# Optotransistor.net
KiCad netlist of a schematic drawn in Altium Designer
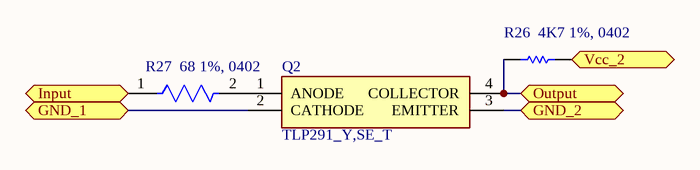
[diagram p0: Optotransistor.SchDoc]

(export (version "E")
  (design (tool "Eeschema 10.0.6"))
  (components
    (comp (ref "Q2")
      (value "TLP291_Y,SE_T")
      (footprint "SamacSys:SOIC127P700X220-4N")
      (description "Phototransistor")
      (fields (field (name "MANUFACTURER_PART_NUMBER") "TLP291(Y,SE(T"))
      (libsource (lib "*") (part "TLP291_Y,SE_T"))
    )
    (comp (ref "R26")
      (value "4K7 1%, 0402")
      (footprint "RESC1005X40X25LL05T05")
      (description "Chip Resistor, 4.7 KOhm, +/- 1%, 0.1 W, -55 to 155 degC, 0402 (1005 Metric), RoHS, Tape and Reel")
      (fields (field (name "TOLERANCE") "1%") (field (name "PARTNUMBER") "ERJ-2RKF4701X"))
      (libsource (lib "Altium Content Vault") (part "RES-2"))
    )
    (comp (ref "R27")
      (value "68 1%, 0402")
      (footprint "FP-ERJ2RK-MFG")
      (fields (field (name "TOLERANCE") "1%"))
      (libsource (lib "Altium Content Vault") (part "1029c3af85768c4190bb7ad29bc67b5"))
    )
  )
  (nets
    (net (code "1") (name "/GND_1") (class "Default")
      (node (ref "Q2") (pin "2") (pinfunction "CATHODE_2") (pintype "passive"))
    )
    (net (code "2") (name "/GND_2") (class "Default")
      (node (ref "Q2") (pin "3") (pinfunction "EMITTER_3") (pintype "passive"))
    )
    (net (code "3") (name "/Input") (class "Default")
      (node (ref "R27") (pin "1") (pinfunction "1_1") (pintype "passive"))
    )
    (net (code "4") (name "/Output") (class "Default")
      (node (ref "Q2") (pin "4") (pinfunction "COLLECTOR_4") (pintype "passive"))
      (node (ref "R26") (pin "2") (pinfunction "2_2") (pintype "passive"))
    )
    (net (code "5") (name "/Vcc_2") (class "Default")
      (node (ref "R26") (pin "1") (pinfunction "1_1") (pintype "passive"))
    )
    (net (code "6") (name "Net-(Q2-ANODE)") (class "Default")
      (node (ref "Q2") (pin "1") (pinfunction "ANODE_1") (pintype "passive"))
      (node (ref "R27") (pin "2") (pinfunction "2_2") (pintype "passive"))
    )
  )
)
